# accelerometer.net
KiCad netlist of a schematic drawn in Altium Designer
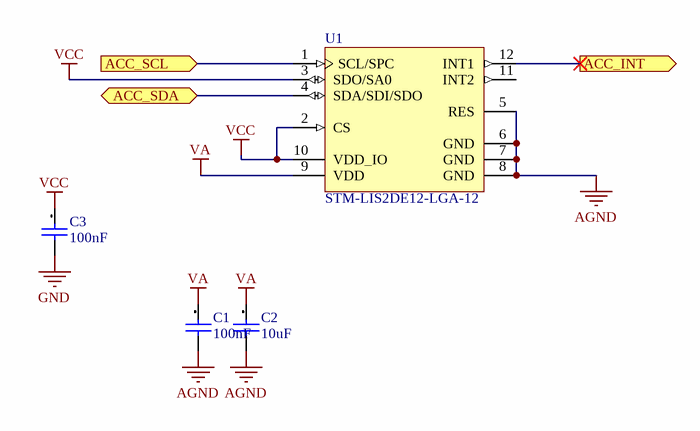
[diagram p0: accelerometer.SchDoc]

(export (version "E")
  (design (tool "Eeschema 10.0.6"))
  (components
    (comp (ref "C1")
      (value "100nF")
      (footprint "CAPC1005X05N")
      (description "Capacitor")
      (fields (field (name "MANUFACTURER") "Kemet") (field (name "VOLTAGE") "50"))
      (libsource (lib "LSRO1Altium") (part "CAP-NP"))
    )
    (comp (ref "C2")
      (value "10uF")
      (footprint "CAPC1005X05N")
      (description "Capacitor")
      (fields (field (name "MANUFACTURER") "Taiyo Yuden") (field (name "VOLTAGE") "6.3"))
      (libsource (lib "LSRO1Altium") (part "CAP-NP"))
    )
    (comp (ref "C3")
      (value "100nF")
      (footprint "CAPC1005X05N")
      (description "Capacitor")
      (fields (field (name "MANUFACTURER") "Kemet") (field (name "VOLTAGE") "50"))
      (libsource (lib "LSRO1Altium") (part "CAP-NP"))
    )
    (comp (ref "U1")
      (value "STM-LIS2DE12-LGA-12")
      (footprint "STM-LGA-12")
      (libsource (lib "STM-LIS2HH12-LGA-12") (part "STM-LIS2HH12-LGA-12"))
    )
  )
  (nets
    (net (code "1") (name "/ACC_INT") (class "Default")
      (node (ref "U1") (pin "12") (pinfunction "INT1_12") (pintype "output+no_connect"))
    )
    (net (code "2") (name "/ACC_SCL") (class "Default")
      (node (ref "U1") (pin "1") (pinfunction "SCL/SPC_1") (pintype "input"))
    )
    (net (code "3") (name "/ACC_SDA") (class "Default")
      (node (ref "U1") (pin "4") (pinfunction "SDA/SDI/SDO_4") (pintype "bidirectional"))
    )
    (net (code "4") (name "AGND") (class "Default")
      (node (ref "C1") (pin "2") (pinfunction "2_2") (pintype "passive"))
      (node (ref "C2") (pin "2") (pinfunction "2_2") (pintype "passive"))
      (node (ref "U1") (pin "5") (pinfunction "RES_5") (pintype "passive"))
      (node (ref "U1") (pin "6") (pinfunction "GND_6") (pintype "power_in"))
      (node (ref "U1") (pin "7") (pinfunction "GND_7") (pintype "power_in"))
      (node (ref "U1") (pin "8") (pinfunction "GND_8") (pintype "power_in"))
    )
    (net (code "5") (name "GND") (class "Default")
      (node (ref "C3") (pin "2") (pinfunction "2_2") (pintype "passive"))
    )
    (net (code "6") (name "VA") (class "Default")
      (node (ref "C1") (pin "1") (pinfunction "1_1") (pintype "passive"))
      (node (ref "C2") (pin "1") (pinfunction "1_1") (pintype "passive"))
      (node (ref "U1") (pin "9") (pinfunction "VDD_9") (pintype "power_in"))
    )
    (net (code "7") (name "VCC") (class "Default")
      (node (ref "C3") (pin "1") (pinfunction "1_1") (pintype "passive"))
      (node (ref "U1") (pin "10") (pinfunction "VDD_IO_10") (pintype "power_in"))
      (node (ref "U1") (pin "2") (pinfunction "CS_2") (pintype "input"))
      (node (ref "U1") (pin "3") (pinfunction "SDO/SA0_3") (pintype "bidirectional"))
    )
    (net (code "8") (name "unconnected-(U1-INT2-Pad11)") (class "Default")
      (node (ref "U1") (pin "11") (pinfunction "INT2_11") (pintype "output"))
    )
  )
)
